# UnoSensor.net
KiCad netlist of a schematic drawn in EAGLE
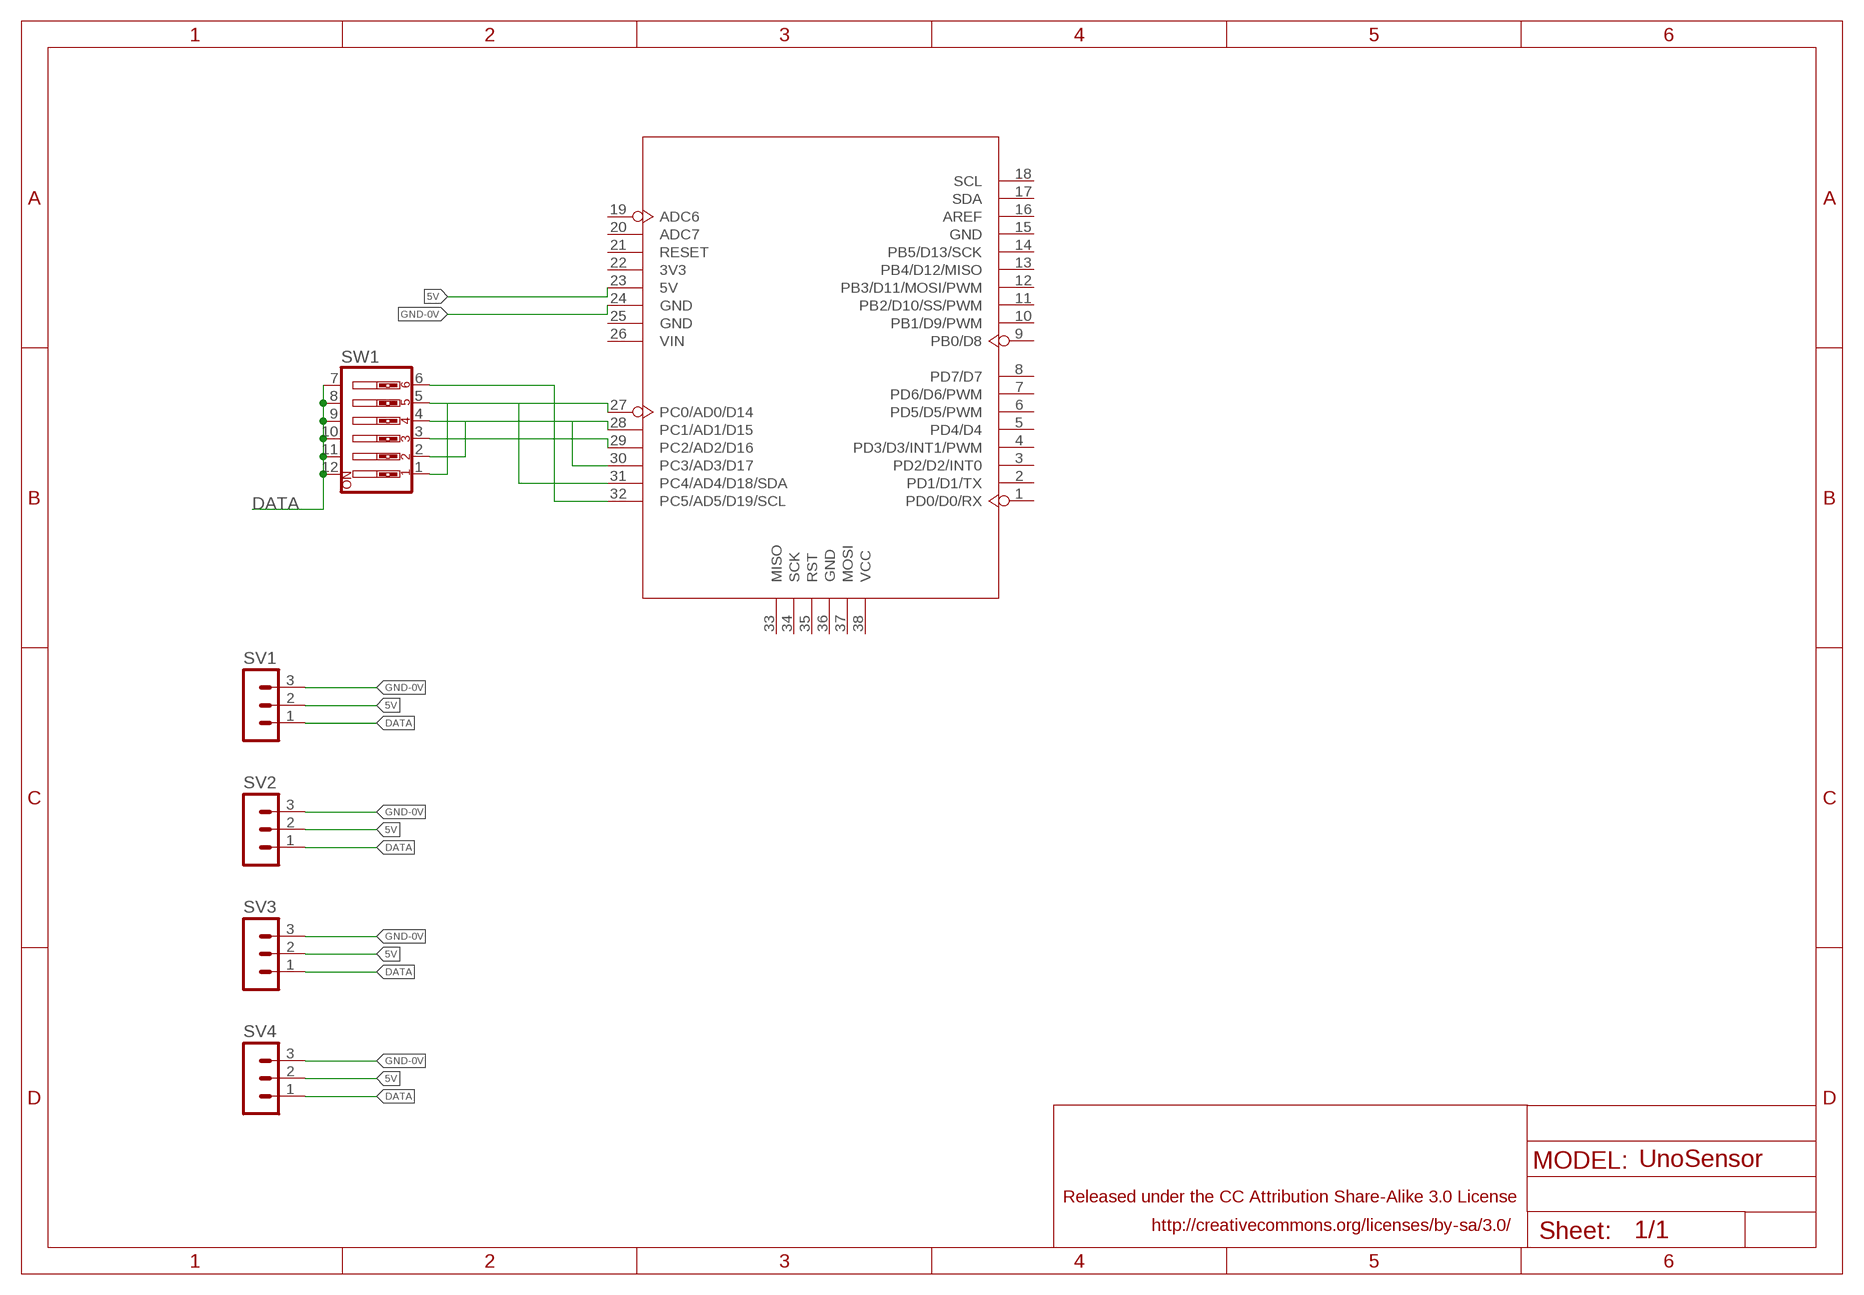
[diagram p0: schematic, sheet 1]

(export (version "E")
  (design (tool "Eeschema 10.0.6"))
  (components
    (comp (ref "SV1")
      (value "2")
      (footprint "eagle-import:MA03-1")
      (libsource (lib "eagle-import") (part "MA03-1"))
    )
    (comp (ref "SV2")
      (value "MA03-1")
      (footprint "eagle-import:MA03-1")
      (libsource (lib "eagle-import") (part "MA03-1"))
    )
    (comp (ref "SV3")
      (value "MA03-1")
      (footprint "eagle-import:MA03-1")
      (libsource (lib "eagle-import") (part "MA03-1"))
    )
    (comp (ref "SV4")
      (value "MA03-1")
      (footprint "eagle-import:MA03-1")
      (libsource (lib "eagle-import") (part "MA03-1"))
    )
    (comp (ref "SW1")
      (value "SW_DIP-6")
      (footprint "eagle-import:EDG-06")
      (libsource (lib "eagle-import") (part "SW_DIP-6"))
    )
    (comp (ref "U5")
      (value "MOUDLE_ARDUINO-38P328P_NO_VIA")
      (footprint "eagle-import:MOUDLE_ARDUINO-328P--")
      (libsource (lib "eagle-import") (part "MOUDLE_ARDUINO-38P328P_NO_VIA"))
    )
  )
  (nets
    (net (code "1") (name "5V") (class "Default")
      (node (ref "SV1") (pin "2") (pinfunction "2_2") (pintype "passive"))
      (node (ref "SV2") (pin "2") (pinfunction "2_2") (pintype "passive"))
      (node (ref "SV3") (pin "2") (pinfunction "2_2") (pintype "passive"))
      (node (ref "SV4") (pin "2") (pinfunction "2_2") (pintype "passive"))
      (node (ref "U5") (pin "23") (pinfunction "5V_23") (pintype "bidirectional"))
    )
    (net (code "2") (name "DATA") (class "Default")
      (node (ref "SV1") (pin "1") (pinfunction "1_1") (pintype "passive"))
      (node (ref "SV2") (pin "1") (pinfunction "1_1") (pintype "passive"))
      (node (ref "SV3") (pin "1") (pinfunction "1_1") (pintype "passive"))
      (node (ref "SV4") (pin "1") (pinfunction "1_1") (pintype "passive"))
      (node (ref "SW1") (pin "10") (pinfunction "10_10") (pintype "passive"))
      (node (ref "SW1") (pin "11") (pinfunction "11_11") (pintype "passive"))
      (node (ref "SW1") (pin "12") (pinfunction "12_12") (pintype "passive"))
      (node (ref "SW1") (pin "7") (pinfunction "7_7") (pintype "passive"))
      (node (ref "SW1") (pin "8") (pinfunction "8_8") (pintype "passive"))
      (node (ref "SW1") (pin "9") (pinfunction "9_9") (pintype "passive"))
    )
    (net (code "3") (name "GND-0V") (class "Default")
      (node (ref "SV1") (pin "3") (pinfunction "3_3") (pintype "passive"))
      (node (ref "SV2") (pin "3") (pinfunction "3_3") (pintype "passive"))
      (node (ref "SV3") (pin "3") (pinfunction "3_3") (pintype "passive"))
      (node (ref "SV4") (pin "3") (pinfunction "3_3") (pintype "passive"))
      (node (ref "U5") (pin "24") (pinfunction "GND_24") (pintype "bidirectional"))
    )
    (net (code "4") (name "Net-(U5-PC0{slash}AD0{slash}D14)") (class "Default")
      (node (ref "SW1") (pin "1") (pinfunction "1_1") (pintype "passive"))
      (node (ref "U5") (pin "27") (pinfunction "PC0/AD0/D14_27") (pintype "bidirectional"))
    )
    (net (code "5") (name "Net-(U5-PC1{slash}AD1{slash}D15)") (class "Default")
      (node (ref "SW1") (pin "2") (pinfunction "2_2") (pintype "passive"))
      (node (ref "U5") (pin "28") (pinfunction "PC1/AD1/D15_28") (pintype "bidirectional"))
    )
    (net (code "6") (name "Net-(U5-PC2{slash}AD2{slash}D16)") (class "Default")
      (node (ref "SW1") (pin "3") (pinfunction "3_3") (pintype "passive"))
      (node (ref "U5") (pin "29") (pinfunction "PC2/AD2/D16_29") (pintype "bidirectional"))
    )
    (net (code "7") (name "Net-(U5-PC3{slash}AD3{slash}D17)") (class "Default")
      (node (ref "SW1") (pin "4") (pinfunction "4_4") (pintype "passive"))
      (node (ref "U5") (pin "30") (pinfunction "PC3/AD3/D17_30") (pintype "bidirectional"))
    )
    (net (code "8") (name "Net-(U5-PC4{slash}AD4{slash}D18{slash}SDA)") (class "Default")
      (node (ref "SW1") (pin "5") (pinfunction "5_5") (pintype "passive"))
      (node (ref "U5") (pin "31") (pinfunction "PC4/AD4/D18/SDA_31") (pintype "bidirectional"))
    )
    (net (code "9") (name "Net-(U5-PC5{slash}AD5{slash}D19{slash}SCL)") (class "Default")
      (node (ref "SW1") (pin "6") (pinfunction "6_6") (pintype "passive"))
      (node (ref "U5") (pin "32") (pinfunction "PC5/AD5/D19/SCL_32") (pintype "bidirectional"))
    )
    (net (code "10") (name "unconnected-(U5-3V3-Pad22)") (class "Default")
      (node (ref "U5") (pin "22") (pinfunction "3V3_22") (pintype "bidirectional"))
    )
    (net (code "11") (name "unconnected-(U5-ADC6-Pad19)") (class "Default")
      (node (ref "U5") (pin "19") (pinfunction "ADC6_19") (pintype "bidirectional"))
    )
    (net (code "12") (name "unconnected-(U5-ADC7-Pad20)") (class "Default")
      (node (ref "U5") (pin "20") (pinfunction "ADC7_20") (pintype "bidirectional"))
    )
    (net (code "13") (name "unconnected-(U5-AREF-Pad16)") (class "Default")
      (node (ref "U5") (pin "16") (pinfunction "AREF_16") (pintype "bidirectional"))
    )
    (net (code "14") (name "unconnected-(U5-GND-Pad15)") (class "Default")
      (node (ref "U5") (pin "15") (pinfunction "GND_15") (pintype "bidirectional"))
    )
    (net (code "15") (name "unconnected-(U5-GND-Pad25)") (class "Default")
      (node (ref "U5") (pin "25") (pinfunction "GND_25") (pintype "bidirectional"))
    )
    (net (code "16") (name "unconnected-(U5-GND-Pad36)") (class "Default")
      (node (ref "U5") (pin "36") (pinfunction "GND_36") (pintype "bidirectional"))
    )
    (net (code "17") (name "unconnected-(U5-MISO-Pad33)") (class "Default")
      (node (ref "U5") (pin "33") (pinfunction "MISO_33") (pintype "bidirectional"))
    )
    (net (code "18") (name "unconnected-(U5-MOSI-Pad37)") (class "Default")
      (node (ref "U5") (pin "37") (pinfunction "MOSI_37") (pintype "bidirectional"))
    )
    (net (code "19") (name "unconnected-(U5-PB0{slash}D8-Pad9)") (class "Default")
      (node (ref "U5") (pin "9") (pinfunction "PB0/D8_9") (pintype "bidirectional"))
    )
    (net (code "20") (name "unconnected-(U5-PB1{slash}D9{slash}PWM-Pad10)") (class "Default")
      (node (ref "U5") (pin "10") (pinfunction "PB1/D9/PWM_10") (pintype "bidirectional"))
    )
    (net (code "21") (name "unconnected-(U5-PB2{slash}D10{slash}SS{slash}PWM-Pad11)") (class "Default")
      (node (ref "U5") (pin "11") (pinfunction "PB2/D10/SS/PWM_11") (pintype "bidirectional"))
    )
    (net (code "22") (name "unconnected-(U5-PB3{slash}D11{slash}MOSI{slash}PWM-Pad12)") (class "Default")
      (node (ref "U5") (pin "12") (pinfunction "PB3/D11/MOSI/PWM_12") (pintype "bidirectional"))
    )
    (net (code "23") (name "unconnected-(U5-PB4{slash}D12{slash}MISO-Pad13)") (class "Default")
      (node (ref "U5") (pin "13") (pinfunction "PB4/D12/MISO_13") (pintype "bidirectional"))
    )
    (net (code "24") (name "unconnected-(U5-PB5{slash}D13{slash}SCK-Pad14)") (class "Default")
      (node (ref "U5") (pin "14") (pinfunction "PB5/D13/SCK_14") (pintype "bidirectional"))
    )
    (net (code "25") (name "unconnected-(U5-PD0{slash}D0{slash}RX-Pad1)") (class "Default")
      (node (ref "U5") (pin "1") (pinfunction "PD0/D0/RX_1") (pintype "bidirectional"))
    )
    (net (code "26") (name "unconnected-(U5-PD1{slash}D1{slash}TX-Pad2)") (class "Default")
      (node (ref "U5") (pin "2") (pinfunction "PD1/D1/TX_2") (pintype "bidirectional"))
    )
    (net (code "27") (name "unconnected-(U5-PD2{slash}D2{slash}INT0-Pad3)") (class "Default")
      (node (ref "U5") (pin "3") (pinfunction "PD2/D2/INT0_3") (pintype "bidirectional"))
    )
    (net (code "28") (name "unconnected-(U5-PD3{slash}D3{slash}INT1{slash}PWM-Pad4)") (class "Default")
      (node (ref "U5") (pin "4") (pinfunction "PD3/D3/INT1/PWM_4") (pintype "bidirectional"))
    )
    (net (code "29") (name "unconnected-(U5-PD4{slash}D4-Pad5)") (class "Default")
      (node (ref "U5") (pin "5") (pinfunction "PD4/D4_5") (pintype "bidirectional"))
    )
    (net (code "30") (name "unconnected-(U5-PD5{slash}D5{slash}PWM-Pad6)") (class "Default")
      (node (ref "U5") (pin "6") (pinfunction "PD5/D5/PWM_6") (pintype "bidirectional"))
    )
    (net (code "31") (name "unconnected-(U5-PD6{slash}D6{slash}PWM-Pad7)") (class "Default")
      (node (ref "U5") (pin "7") (pinfunction "PD6/D6/PWM_7") (pintype "bidirectional"))
    )
    (net (code "32") (name "unconnected-(U5-PD7{slash}D7-Pad8)") (class "Default")
      (node (ref "U5") (pin "8") (pinfunction "PD7/D7_8") (pintype "bidirectional"))
    )
    (net (code "33") (name "unconnected-(U5-RESET-Pad21)") (class "Default")
      (node (ref "U5") (pin "21") (pinfunction "RESET_21") (pintype "bidirectional"))
    )
    (net (code "34") (name "unconnected-(U5-RST-Pad35)") (class "Default")
      (node (ref "U5") (pin "35") (pinfunction "RST_35") (pintype "bidirectional"))
    )
    (net (code "35") (name "unconnected-(U5-SCK-Pad34)") (class "Default")
      (node (ref "U5") (pin "34") (pinfunction "SCK_34") (pintype "bidirectional"))
    )
    (net (code "36") (name "unconnected-(U5-SCL-Pad18)") (class "Default")
      (node (ref "U5") (pin "18") (pinfunction "SCL_18") (pintype "bidirectional"))
    )
    (net (code "37") (name "unconnected-(U5-SDA-Pad17)") (class "Default")
      (node (ref "U5") (pin "17") (pinfunction "SDA_17") (pintype "bidirectional"))
    )
    (net (code "38") (name "unconnected-(U5-VCC-Pad38)") (class "Default")
      (node (ref "U5") (pin "38") (pinfunction "VCC_38") (pintype "bidirectional"))
    )
    (net (code "39") (name "unconnected-(U5-VIN-Pad26)") (class "Default")
      (node (ref "U5") (pin "26") (pinfunction "VIN_26") (pintype "bidirectional"))
    )
  )
)
